# circuit_page19.net
KiCad netlist of a schematic drawn in Altium Designer
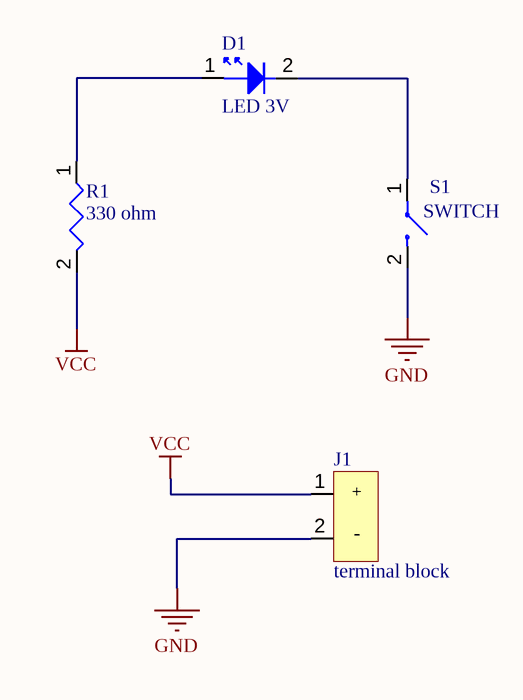
[diagram p0: circuit page19.SchDoc]

(export (version "E")
  (design (tool "Eeschema 10.0.6"))
  (components
    (comp (ref "D1") (value "LED 3V") (footprint "led TH") (libsource (lib "circuit19") (part "led_TH")))
    (comp (ref "J1")
      (value "terminal block")
      (footprint "header")
      (libsource (lib "circuit19") (part "terminal block_TH"))
    )
    (comp (ref "R1")
      (value "330 ohm")
      (footprint "330ohm_TH")
      (description "through hole resistor 330 ohm")
      (fields
        (field (name "MANUFACTURER") "TE Connectivity Passive Product")
        (field (name "TOLERANCE") "±1%")
      )
      (libsource (lib "circuit19") (part "resistor_TH"))
    )
    (comp (ref "S1")
      (value "SWITCH")
      (footprint "DIP1")
      (description "DIP SWITCH")
      (libsource (lib "circuit19") (part "dip swith1_TH"))
    )
  )
  (nets
    (net (code "1") (name "GND") (class "Default")
      (node (ref "J1") (pin "2") (pintype "passive"))
      (node (ref "S1") (pin "2") (pintype "passive"))
    )
    (net (code "2") (name "Net-(D1-Pad1)") (class "Default")
      (node (ref "D1") (pin "1") (pintype "passive"))
      (node (ref "R1") (pin "1") (pintype "passive"))
    )
    (net (code "3") (name "Net-(D1-Pad2)") (class "Default")
      (node (ref "D1") (pin "2") (pintype "passive"))
      (node (ref "S1") (pin "1") (pintype "passive"))
    )
    (net (code "4") (name "VCC") (class "Default")
      (node (ref "J1") (pin "1") (pintype "passive"))
      (node (ref "R1") (pin "2") (pintype "passive"))
    )
  )
)
